# slave_relais.net
KiCad netlist of a schematic drawn in EAGLE
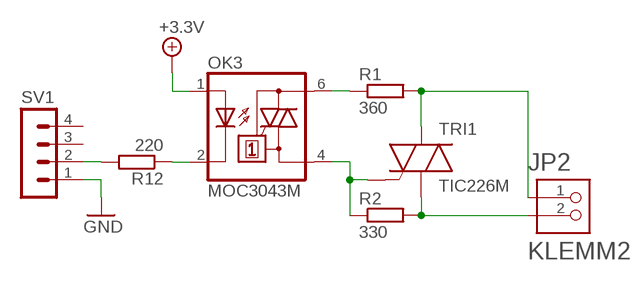
[diagram p0: schematic, sheet 1]

(export (version "E")
  (design (tool "Eeschema 10.0.6"))
  (components
    (comp (ref "JP2")
      (value "KLEMM2")
      (footprint "eagle-import:KLEMM2")
      (libsource (lib "eagle-import") (part "KLEMM2"))
    )
    (comp (ref "OK3")
      (value "MOC3043M")
      (footprint "eagle-import:DIL06")
      (fields (field (name "MF") "FAIRCHILD SEMICONDUCTOR") (field (name "MPN") "MOC3043-M"))
      (libsource (lib "eagle-import") (part "MOC3043M"))
    )
    (comp (ref "R1")
      (value "360")
      (footprint "eagle-import:0204_7")
      (libsource (lib "eagle-import") (part "R-EU_0204/7"))
    )
    (comp (ref "R2")
      (value "330")
      (footprint "eagle-import:0204_7")
      (libsource (lib "eagle-import") (part "R-EU_0204/7"))
    )
    (comp (ref "R12")
      (value "220")
      (footprint "eagle-import:0207_12")
      (libsource (lib "eagle-import") (part "R-EU_0207/12"))
    )
    (comp (ref "SV1")
      (value "MA04-1")
      (footprint "eagle-import:MA04-1")
      (libsource (lib "eagle-import") (part "MA04-1"))
    )
    (comp (ref "TRI1")
      (value "TIC226M")
      (footprint "eagle-import:TO-220A")
      (libsource (lib "eagle-import") (part "TIC226M"))
    )
  )
  (nets
    (net (code "1") (name "+3.3V") (class "Default")
      (node (ref "OK3") (pin "1") (pinfunction "A_1") (pintype "passive"))
    )
    (net (code "2") (name "GND") (class "Default")
      (node (ref "SV1") (pin "1") (pinfunction "1_1") (pintype "passive"))
    )
    (net (code "3") (name "Net-(OK3-A1)") (class "Default")
      (node (ref "OK3") (pin "4") (pinfunction "A1_4") (pintype "passive"))
      (node (ref "R2") (pin "1") (pinfunction "1_1") (pintype "passive"))
      (node (ref "TRI1") (pin "3") (pinfunction "G_3") (pintype "passive"))
    )
    (net (code "4") (name "Net-(OK3-A2)") (class "Default")
      (node (ref "OK3") (pin "6") (pinfunction "A2_6") (pintype "passive"))
      (node (ref "R1") (pin "1") (pinfunction "1_1") (pintype "passive"))
    )
    (net (code "5") (name "Net-(OK3-C)") (class "Default")
      (node (ref "OK3") (pin "2") (pinfunction "C_2") (pintype "passive"))
      (node (ref "R12") (pin "1") (pinfunction "1_1") (pintype "passive"))
    )
    (net (code "6") (name "Net-(R12-Pad2)") (class "Default")
      (node (ref "R12") (pin "2") (pinfunction "2_2") (pintype "passive"))
      (node (ref "SV1") (pin "2") (pinfunction "2_2") (pintype "passive"))
    )
    (net (code "7") (name "Net-(TRI1-A1)") (class "Default")
      (node (ref "JP2") (pin "2") (pinfunction "2_2") (pintype "passive"))
      (node (ref "R2") (pin "2") (pinfunction "2_2") (pintype "passive"))
      (node (ref "TRI1") (pin "1") (pinfunction "A1_1") (pintype "passive"))
    )
    (net (code "8") (name "Net-(TRI1-A2)") (class "Default")
      (node (ref "JP2") (pin "1") (pinfunction "1_1") (pintype "passive"))
      (node (ref "R1") (pin "2") (pinfunction "2_2") (pintype "passive"))
      (node (ref "TRI1") (pin "2") (pinfunction "A2_2") (pintype "passive"))
    )
    (net (code "9") (name "unconnected-(SV1-Pad3)") (class "Default")
      (node (ref "SV1") (pin "3") (pinfunction "3_3") (pintype "passive"))
    )
    (net (code "10") (name "unconnected-(SV1-Pad4)") (class "Default")
      (node (ref "SV1") (pin "4") (pinfunction "4_4") (pintype "passive"))
    )
  )
)
